# Temp1.net
KiCad netlist of a schematic drawn in EAGLE
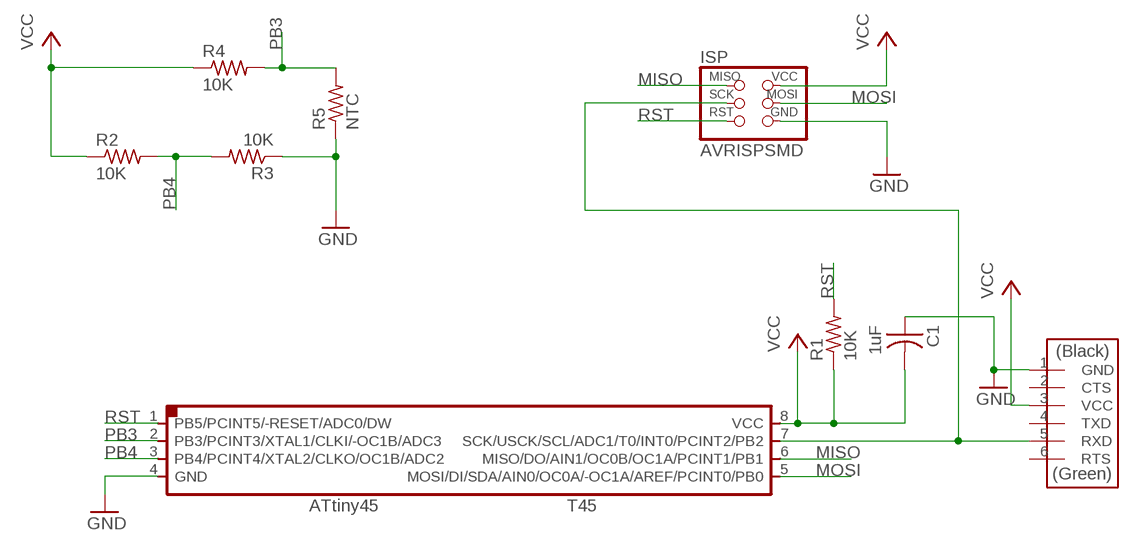
[diagram p0: schematic, sheet 1]

(export (version "E")
  (design (tool "Eeschema 10.0.6"))
  (components
    (comp (ref "C1")
      (value "1uF")
      (footprint "eagle-import:C1206FAB")
      (libsource (lib "eagle-import") (part "CAP-US1206FAB"))
    )
    (comp (ref "FDTI")
      (value "FTDI-SMD-HEADER")
      (footprint "eagle-import:1X06SMD")
      (libsource (lib "eagle-import") (part "FTDI-SMD-HEADER"))
    )
    (comp (ref "ISP")
      (value "AVRISPSMD")
      (footprint "eagle-import:2X03SMD")
      (libsource (lib "eagle-import") (part "AVRISPSMD"))
    )
    (comp (ref "R1")
      (value "10K")
      (footprint "eagle-import:R1206FAB")
      (libsource (lib "eagle-import") (part "RES-US1206FAB"))
    )
    (comp (ref "R2")
      (value "10K")
      (footprint "eagle-import:R1206FAB")
      (libsource (lib "eagle-import") (part "RES-US1206FAB"))
    )
    (comp (ref "R3")
      (value "10K")
      (footprint "eagle-import:R1206FAB")
      (libsource (lib "eagle-import") (part "RES-US1206FAB"))
    )
    (comp (ref "R4")
      (value "10K")
      (footprint "eagle-import:R1206FAB")
      (libsource (lib "eagle-import") (part "RES-US1206FAB"))
    )
    (comp (ref "R5")
      (value "NTC")
      (footprint "eagle-import:R1206FAB")
      (libsource (lib "eagle-import") (part "RES-US1206FAB"))
    )
    (comp (ref "T45")
      (value "ATTINY45SI")
      (footprint "eagle-import:SOIC8")
      (libsource (lib "eagle-import") (part "ATTINY45SI"))
    )
  )
  (nets
    (net (code "1") (name "/MISO") (class "Default")
      (node (ref "ISP") (pin "1") (pinfunction "MISO_1") (pintype "passive"))
      (node (ref "T45") (pin "6") (pinfunction "MISO/DO/AIN1/OC0B/OC1A/PCINT1/PB1_6") (pintype "bidirectional"))
    )
    (net (code "2") (name "/MOSI") (class "Default")
      (node (ref "ISP") (pin "4") (pinfunction "MOSI_4") (pintype "passive"))
      (node (ref "T45") (pin "5") (pinfunction "MOSI/DI/SDA/AIN0/OC0A/-OC1A/AREF/PCINT0/PB0_5") (pintype "bidirectional"))
    )
    (net (code "3") (name "/PB3") (class "Default")
      (node (ref "R4") (pin "2") (pinfunction "2_2") (pintype "passive"))
      (node (ref "R5") (pin "2") (pinfunction "2_2") (pintype "passive"))
      (node (ref "T45") (pin "2") (pinfunction "PB3/PCINT3/XTAL1/CLKI/-OC1B/ADC3_2") (pintype "bidirectional"))
    )
    (net (code "4") (name "/PB4") (class "Default")
      (node (ref "R2") (pin "2") (pinfunction "2_2") (pintype "passive"))
      (node (ref "R3") (pin "2") (pinfunction "2_2") (pintype "passive"))
      (node (ref "T45") (pin "3") (pinfunction "PB4/PCINT4/XTAL2/CLKO/OC1B/ADC2_3") (pintype "bidirectional"))
    )
    (net (code "5") (name "/RST") (class "Default")
      (node (ref "ISP") (pin "5") (pinfunction "RST_5") (pintype "passive"))
      (node (ref "R1") (pin "2") (pinfunction "2_2") (pintype "passive"))
      (node (ref "T45") (pin "1") (pinfunction "PB5/PCINT5/-RESET/ADC0/DW_1") (pintype "bidirectional"))
    )
    (net (code "6") (name "GND") (class "Default")
      (node (ref "C1") (pin "1") (pinfunction "1_1") (pintype "passive"))
      (node (ref "FDTI") (pin "1") (pinfunction "GND_1") (pintype "bidirectional"))
      (node (ref "ISP") (pin "6") (pinfunction "GND_6") (pintype "passive"))
      (node (ref "R3") (pin "1") (pinfunction "1_1") (pintype "passive"))
      (node (ref "R5") (pin "1") (pinfunction "1_1") (pintype "passive"))
      (node (ref "T45") (pin "4") (pinfunction "GND_4") (pintype "bidirectional"))
    )
    (net (code "7") (name "Net-(FDTI-RXD)") (class "Default")
      (node (ref "FDTI") (pin "5") (pinfunction "RXD_5") (pintype "bidirectional"))
      (node (ref "ISP") (pin "3") (pinfunction "SCK_3") (pintype "passive"))
      (node (ref "T45") (pin "7") (pinfunction "SCK/USCK/SCL/ADC1/T0/INT0/PCINT2/PB2_7") (pintype "bidirectional"))
    )
    (net (code "8") (name "VCC") (class "Default")
      (node (ref "C1") (pin "2") (pinfunction "2_2") (pintype "passive"))
      (node (ref "FDTI") (pin "3") (pinfunction "VCC_3") (pintype "bidirectional"))
      (node (ref "ISP") (pin "2") (pinfunction "VCC_2") (pintype "passive"))
      (node (ref "R1") (pin "1") (pinfunction "1_1") (pintype "passive"))
      (node (ref "R2") (pin "1") (pinfunction "1_1") (pintype "passive"))
      (node (ref "R4") (pin "1") (pinfunction "1_1") (pintype "passive"))
      (node (ref "T45") (pin "8") (pinfunction "VCC_8") (pintype "bidirectional"))
    )
    (net (code "9") (name "unconnected-(FDTI-CTS-Pad2)") (class "Default")
      (node (ref "FDTI") (pin "2") (pinfunction "CTS_2") (pintype "bidirectional"))
    )
    (net (code "10") (name "unconnected-(FDTI-RTS-Pad6)") (class "Default")
      (node (ref "FDTI") (pin "6") (pinfunction "RTS_6") (pintype "bidirectional"))
    )
    (net (code "11") (name "unconnected-(FDTI-TXD-Pad4)") (class "Default")
      (node (ref "FDTI") (pin "4") (pinfunction "TXD_4") (pintype "bidirectional"))
    )
  )
)
